# VS1053_Demo.net
KiCad netlist of a schematic drawn in EAGLE
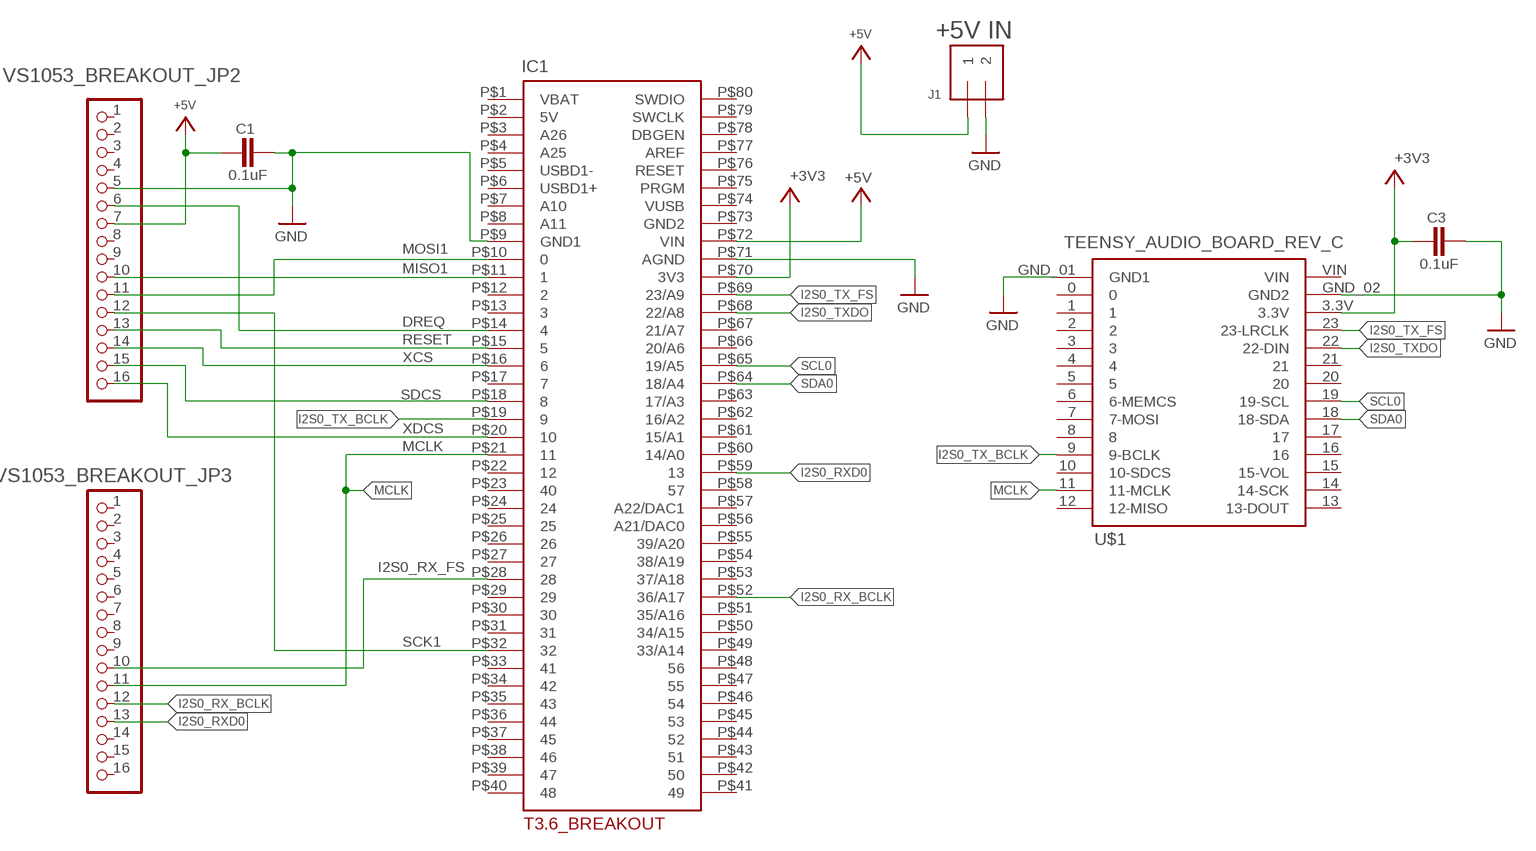
[diagram p0: schematic, sheet 1]

(export (version "E")
  (design (tool "Eeschema 10.0.6"))
  (components
    (comp (ref "C1")
      (value "0.1uF")
      (footprint "eagle-import:CAP-PTH-SMALL-KIT")
      (libsource (lib "eagle-import") (part "0.1UF-KIT-EZ-50V-20%"))
    )
    (comp (ref "C3")
      (value "0.1uF")
      (footprint "eagle-import:CAP-PTH-SMALL-KIT")
      (libsource (lib "eagle-import") (part "0.1UF-KIT-EZ-50V-20%"))
    )
    (comp (ref "IC1")
      (value "T3.6_BREAKOUT")
      (footprint "eagle-import:T3.6_BREAKOUT")
      (libsource (lib "eagle-import") (part "T3.6_BREAKOUT"))
    )
    (comp (ref "J1")
      (value "TERMBLOCK_1X2")
      (footprint "eagle-import:TERMBLOCK_1X2-3.5MM")
      (libsource (lib "eagle-import") (part "TERMBLOCK_1X2"))
    )
    (comp (ref "U$1")
      (value "TEENSY_AUDIO_BOARD_REV_C")
      (footprint "eagle-import:TEENSY_AUDIO_BOARD")
      (libsource (lib "eagle-import") (part "TEENSY_AUDIO_BOARD_REV_C"))
    )
    (comp (ref "VS1053_BREAKOUT_JP2")
      (value "HEADER-1X16ROUND")
      (footprint "eagle-import:1X16_ROUND")
      (libsource (lib "eagle-import") (part "HEADER-1X16ROUND"))
    )
    (comp (ref "VS1053_BREAKOUT_JP3")
      (value "HEADER-1X16ROUND")
      (footprint "eagle-import:1X16_ROUND")
      (libsource (lib "eagle-import") (part "HEADER-1X16ROUND"))
    )
  )
  (nets
    (net (code "1") (name "+3V3") (class "Default")
      (node (ref "C3") (pin "1") (pinfunction "1_1") (pintype "passive"))
      (node (ref "IC1") (pin "P$70") (pinfunction "3V3_P$70") (pintype "bidirectional"))
      (node (ref "U$1") (pin "3.3V") (pinfunction "3.3V_3.3V") (pintype "bidirectional"))
    )
    (net (code "2") (name "+5V") (class "Default")
      (node (ref "C1") (pin "1") (pinfunction "1_1") (pintype "passive"))
      (node (ref "IC1") (pin "P$72") (pinfunction "VIN_P$72") (pintype "bidirectional"))
      (node (ref "J1") (pin "1") (pinfunction "1_1") (pintype "passive"))
      (node (ref "VS1053_BREAKOUT_JP2") (pin "7") (pinfunction "7_7") (pintype "passive"))
    )
    (net (code "3") (name "/DREQ") (class "Default")
      (node (ref "IC1") (pin "P$14") (pinfunction "4_P$14") (pintype "bidirectional"))
      (node (ref "VS1053_BREAKOUT_JP2") (pin "6") (pinfunction "6_6") (pintype "passive"))
    )
    (net (code "4") (name "/I2S0_RX_FS") (class "Default")
      (node (ref "IC1") (pin "P$28") (pinfunction "28_P$28") (pintype "bidirectional"))
      (node (ref "VS1053_BREAKOUT_JP3") (pin "10") (pinfunction "10_10") (pintype "passive"))
    )
    (net (code "5") (name "/MISO1") (class "Default")
      (node (ref "IC1") (pin "P$11") (pinfunction "1_P$11") (pintype "bidirectional"))
      (node (ref "VS1053_BREAKOUT_JP2") (pin "10") (pinfunction "10_10") (pintype "passive"))
    )
    (net (code "6") (name "/MOSI1") (class "Default")
      (node (ref "IC1") (pin "P$10") (pinfunction "0_P$10") (pintype "bidirectional"))
      (node (ref "VS1053_BREAKOUT_JP2") (pin "11") (pinfunction "11_11") (pintype "passive"))
    )
    (net (code "7") (name "/RESET") (class "Default")
      (node (ref "IC1") (pin "P$15") (pinfunction "5_P$15") (pintype "bidirectional"))
      (node (ref "VS1053_BREAKOUT_JP2") (pin "13") (pinfunction "13_13") (pintype "passive"))
    )
    (net (code "8") (name "/SCK1") (class "Default")
      (node (ref "IC1") (pin "P$32") (pinfunction "32_P$32") (pintype "bidirectional"))
      (node (ref "VS1053_BREAKOUT_JP2") (pin "12") (pinfunction "12_12") (pintype "passive"))
    )
    (net (code "9") (name "/SDCS") (class "Default")
      (node (ref "IC1") (pin "P$18") (pinfunction "8_P$18") (pintype "bidirectional"))
      (node (ref "VS1053_BREAKOUT_JP2") (pin "15") (pinfunction "15_15") (pintype "passive"))
    )
    (net (code "10") (name "/XCS") (class "Default")
      (node (ref "IC1") (pin "P$16") (pinfunction "6_P$16") (pintype "bidirectional"))
      (node (ref "VS1053_BREAKOUT_JP2") (pin "14") (pinfunction "14_14") (pintype "passive"))
    )
    (net (code "11") (name "/XDCS") (class "Default")
      (node (ref "IC1") (pin "P$20") (pinfunction "10_P$20") (pintype "bidirectional"))
      (node (ref "VS1053_BREAKOUT_JP2") (pin "16") (pinfunction "16_16") (pintype "passive"))
    )
    (net (code "12") (name "GND") (class "Default")
      (node (ref "C1") (pin "2") (pinfunction "2_2") (pintype "passive"))
      (node (ref "C3") (pin "2") (pinfunction "2_2") (pintype "passive"))
      (node (ref "IC1") (pin "P$71") (pinfunction "AGND_P$71") (pintype "bidirectional"))
      (node (ref "IC1") (pin "P$9") (pinfunction "GND1_P$9") (pintype "bidirectional"))
      (node (ref "J1") (pin "2") (pinfunction "2_2") (pintype "passive"))
      (node (ref "U$1") (pin "GND_01") (pinfunction "GND1_GND_01") (pintype "bidirectional"))
      (node (ref "U$1") (pin "GND_02") (pinfunction "GND2_GND_02") (pintype "bidirectional"))
      (node (ref "VS1053_BREAKOUT_JP2") (pin "5") (pinfunction "5_5") (pintype "passive"))
    )
    (net (code "13") (name "I2S0_RXD0") (class "Default")
      (node (ref "IC1") (pin "P$59") (pinfunction "13_P$59") (pintype "bidirectional"))
      (node (ref "VS1053_BREAKOUT_JP3") (pin "13") (pinfunction "13_13") (pintype "passive"))
    )
    (net (code "14") (name "I2S0_RX_BCLK") (class "Default")
      (node (ref "IC1") (pin "P$52") (pinfunction "36/A17_P$52") (pintype "bidirectional"))
      (node (ref "VS1053_BREAKOUT_JP3") (pin "12") (pinfunction "12_12") (pintype "passive"))
    )
    (net (code "15") (name "I2S0_TXDO") (class "Default")
      (node (ref "IC1") (pin "P$68") (pinfunction "22/A8_P$68") (pintype "bidirectional"))
      (node (ref "U$1") (pin "22") (pinfunction "22-DIN_22") (pintype "bidirectional"))
    )
    (net (code "16") (name "I2S0_TX_BCLK") (class "Default")
      (node (ref "IC1") (pin "P$19") (pinfunction "9_P$19") (pintype "bidirectional"))
      (node (ref "U$1") (pin "9") (pinfunction "9-BCLK_9") (pintype "bidirectional"))
    )
    (net (code "17") (name "I2S0_TX_FS") (class "Default")
      (node (ref "IC1") (pin "P$69") (pinfunction "23/A9_P$69") (pintype "bidirectional"))
      (node (ref "U$1") (pin "23") (pinfunction "23-LRCLK_23") (pintype "bidirectional"))
    )
    (net (code "18") (name "MCLK") (class "Default")
      (node (ref "IC1") (pin "P$21") (pinfunction "11_P$21") (pintype "bidirectional"))
      (node (ref "U$1") (pin "11") (pinfunction "11-MCLK_11") (pintype "bidirectional"))
      (node (ref "VS1053_BREAKOUT_JP3") (pin "11") (pinfunction "11_11") (pintype "passive"))
    )
    (net (code "19") (name "SCL0") (class "Default")
      (node (ref "IC1") (pin "P$65") (pinfunction "19/A5_P$65") (pintype "bidirectional"))
      (node (ref "U$1") (pin "19") (pinfunction "19-SCL_19") (pintype "bidirectional"))
    )
    (net (code "20") (name "SDA0") (class "Default")
      (node (ref "IC1") (pin "P$64") (pinfunction "18/A4_P$64") (pintype "bidirectional"))
      (node (ref "U$1") (pin "18") (pinfunction "18-SDA_18") (pintype "bidirectional"))
    )
    (net (code "21") (name "unconnected-(IC1-2-PadP$12)") (class "Default")
      (node (ref "IC1") (pin "P$12") (pinfunction "2_P$12") (pintype "bidirectional"))
    )
    (net (code "22") (name "unconnected-(IC1-3-PadP$13)") (class "Default")
      (node (ref "IC1") (pin "P$13") (pinfunction "3_P$13") (pintype "bidirectional"))
    )
    (net (code "23") (name "unconnected-(IC1-5V-PadP$2)") (class "Default")
      (node (ref "IC1") (pin "P$2") (pinfunction "5V_P$2") (pintype "bidirectional"))
    )
    (net (code "24") (name "unconnected-(IC1-7-PadP$17)") (class "Default")
      (node (ref "IC1") (pin "P$17") (pinfunction "7_P$17") (pintype "bidirectional"))
    )
    (net (code "25") (name "unconnected-(IC1-12-PadP$22)") (class "Default")
      (node (ref "IC1") (pin "P$22") (pinfunction "12_P$22") (pintype "bidirectional"))
    )
    (net (code "26") (name "unconnected-(IC1-14{slash}A0-PadP$60)") (class "Default")
      (node (ref "IC1") (pin "P$60") (pinfunction "14/A0_P$60") (pintype "bidirectional"))
    )
    (net (code "27") (name "unconnected-(IC1-15{slash}A1-PadP$61)") (class "Default")
      (node (ref "IC1") (pin "P$61") (pinfunction "15/A1_P$61") (pintype "bidirectional"))
    )
    (net (code "28") (name "unconnected-(IC1-16{slash}A2-PadP$62)") (class "Default")
      (node (ref "IC1") (pin "P$62") (pinfunction "16/A2_P$62") (pintype "bidirectional"))
    )
    (net (code "29") (name "unconnected-(IC1-17{slash}A3-PadP$63)") (class "Default")
      (node (ref "IC1") (pin "P$63") (pinfunction "17/A3_P$63") (pintype "bidirectional"))
    )
    (net (code "30") (name "unconnected-(IC1-20{slash}A6-PadP$66)") (class "Default")
      (node (ref "IC1") (pin "P$66") (pinfunction "20/A6_P$66") (pintype "bidirectional"))
    )
    (net (code "31") (name "unconnected-(IC1-21{slash}A7-PadP$67)") (class "Default")
      (node (ref "IC1") (pin "P$67") (pinfunction "21/A7_P$67") (pintype "bidirectional"))
    )
    (net (code "32") (name "unconnected-(IC1-24-PadP$24)") (class "Default")
      (node (ref "IC1") (pin "P$24") (pinfunction "24_P$24") (pintype "bidirectional"))
    )
    (net (code "33") (name "unconnected-(IC1-25-PadP$25)") (class "Default")
      (node (ref "IC1") (pin "P$25") (pinfunction "25_P$25") (pintype "bidirectional"))
    )
    (net (code "34") (name "unconnected-(IC1-26-PadP$26)") (class "Default")
      (node (ref "IC1") (pin "P$26") (pinfunction "26_P$26") (pintype "bidirectional"))
    )
    (net (code "35") (name "unconnected-(IC1-27-PadP$27)") (class "Default")
      (node (ref "IC1") (pin "P$27") (pinfunction "27_P$27") (pintype "bidirectional"))
    )
    (net (code "36") (name "unconnected-(IC1-29-PadP$29)") (class "Default")
      (node (ref "IC1") (pin "P$29") (pinfunction "29_P$29") (pintype "bidirectional"))
    )
    (net (code "37") (name "unconnected-(IC1-30-PadP$30)") (class "Default")
      (node (ref "IC1") (pin "P$30") (pinfunction "30_P$30") (pintype "bidirectional"))
    )
    (net (code "38") (name "unconnected-(IC1-31-PadP$31)") (class "Default")
      (node (ref "IC1") (pin "P$31") (pinfunction "31_P$31") (pintype "bidirectional"))
    )
    (net (code "39") (name "unconnected-(IC1-33{slash}A14-PadP$49)") (class "Default")
      (node (ref "IC1") (pin "P$49") (pinfunction "33/A14_P$49") (pintype "bidirectional"))
    )
    (net (code "40") (name "unconnected-(IC1-34{slash}A15-PadP$50)") (class "Default")
      (node (ref "IC1") (pin "P$50") (pinfunction "34/A15_P$50") (pintype "bidirectional"))
    )
    (net (code "41") (name "unconnected-(IC1-35{slash}A16-PadP$51)") (class "Default")
      (node (ref "IC1") (pin "P$51") (pinfunction "35/A16_P$51") (pintype "bidirectional"))
    )
    (net (code "42") (name "unconnected-(IC1-37{slash}A18-PadP$53)") (class "Default")
      (node (ref "IC1") (pin "P$53") (pinfunction "37/A18_P$53") (pintype "bidirectional"))
    )
    (net (code "43") (name "unconnected-(IC1-38{slash}A19-PadP$54)") (class "Default")
      (node (ref "IC1") (pin "P$54") (pinfunction "38/A19_P$54") (pintype "bidirectional"))
    )
    (net (code "44") (name "unconnected-(IC1-39{slash}A20-PadP$55)") (class "Default")
      (node (ref "IC1") (pin "P$55") (pinfunction "39/A20_P$55") (pintype "bidirectional"))
    )
    (net (code "45") (name "unconnected-(IC1-40-PadP$23)") (class "Default")
      (node (ref "IC1") (pin "P$23") (pinfunction "40_P$23") (pintype "bidirectional"))
    )
    (net (code "46") (name "unconnected-(IC1-41-PadP$33)") (class "Default")
      (node (ref "IC1") (pin "P$33") (pinfunction "41_P$33") (pintype "bidirectional"))
    )
    (net (code "47") (name "unconnected-(IC1-42-PadP$34)") (class "Default")
      (node (ref "IC1") (pin "P$34") (pinfunction "42_P$34") (pintype "bidirectional"))
    )
    (net (code "48") (name "unconnected-(IC1-43-PadP$35)") (class "Default")
      (node (ref "IC1") (pin "P$35") (pinfunction "43_P$35") (pintype "bidirectional"))
    )
    (net (code "49") (name "unconnected-(IC1-44-PadP$36)") (class "Default")
      (node (ref "IC1") (pin "P$36") (pinfunction "44_P$36") (pintype "bidirectional"))
    )
    (net (code "50") (name "unconnected-(IC1-45-PadP$37)") (class "Default")
      (node (ref "IC1") (pin "P$37") (pinfunction "45_P$37") (pintype "bidirectional"))
    )
    (net (code "51") (name "unconnected-(IC1-46-PadP$38)") (class "Default")
      (node (ref "IC1") (pin "P$38") (pinfunction "46_P$38") (pintype "bidirectional"))
    )
    (net (code "52") (name "unconnected-(IC1-47-PadP$39)") (class "Default")
      (node (ref "IC1") (pin "P$39") (pinfunction "47_P$39") (pintype "bidirectional"))
    )
    (net (code "53") (name "unconnected-(IC1-48-PadP$40)") (class "Default")
      (node (ref "IC1") (pin "P$40") (pinfunction "48_P$40") (pintype "bidirectional"))
    )
    (net (code "54") (name "unconnected-(IC1-49-PadP$41)") (class "Default")
      (node (ref "IC1") (pin "P$41") (pinfunction "49_P$41") (pintype "bidirectional"))
    )
    (net (code "55") (name "unconnected-(IC1-50-PadP$42)") (class "Default")
      (node (ref "IC1") (pin "P$42") (pinfunction "50_P$42") (pintype "bidirectional"))
    )
    (net (code "56") (name "unconnected-(IC1-51-PadP$43)") (class "Default")
      (node (ref "IC1") (pin "P$43") (pinfunction "51_P$43") (pintype "bidirectional"))
    )
    (net (code "57") (name "unconnected-(IC1-52-PadP$44)") (class "Default")
      (node (ref "IC1") (pin "P$44") (pinfunction "52_P$44") (pintype "bidirectional"))
    )
    (net (code "58") (name "unconnected-(IC1-53-PadP$45)") (class "Default")
      (node (ref "IC1") (pin "P$45") (pinfunction "53_P$45") (pintype "bidirectional"))
    )
    (net (code "59") (name "unconnected-(IC1-54-PadP$46)") (class "Default")
      (node (ref "IC1") (pin "P$46") (pinfunction "54_P$46") (pintype "bidirectional"))
    )
    (net (code "60") (name "unconnected-(IC1-55-PadP$47)") (class "Default")
      (node (ref "IC1") (pin "P$47") (pinfunction "55_P$47") (pintype "bidirectional"))
    )
    (net (code "61") (name "unconnected-(IC1-56-PadP$48)") (class "Default")
      (node (ref "IC1") (pin "P$48") (pinfunction "56_P$48") (pintype "bidirectional"))
    )
    (net (code "62") (name "unconnected-(IC1-57-PadP$58)") (class "Default")
      (node (ref "IC1") (pin "P$58") (pinfunction "57_P$58") (pintype "bidirectional"))
    )
    (net (code "63") (name "unconnected-(IC1-A10-PadP$7)") (class "Default")
      (node (ref "IC1") (pin "P$7") (pinfunction "A10_P$7") (pintype "bidirectional"))
    )
    (net (code "64") (name "unconnected-(IC1-A11-PadP$8)") (class "Default")
      (node (ref "IC1") (pin "P$8") (pinfunction "A11_P$8") (pintype "bidirectional"))
    )
    (net (code "65") (name "unconnected-(IC1-A21{slash}DAC0-PadP$56)") (class "Default")
      (node (ref "IC1") (pin "P$56") (pinfunction "A21/DAC0_P$56") (pintype "bidirectional"))
    )
    (net (code "66") (name "unconnected-(IC1-A22{slash}DAC1-PadP$57)") (class "Default")
      (node (ref "IC1") (pin "P$57") (pinfunction "A22/DAC1_P$57") (pintype "bidirectional"))
    )
    (net (code "67") (name "unconnected-(IC1-A25-PadP$4)") (class "Default")
      (node (ref "IC1") (pin "P$4") (pinfunction "A25_P$4") (pintype "bidirectional"))
    )
    (net (code "68") (name "unconnected-(IC1-A26-PadP$3)") (class "Default")
      (node (ref "IC1") (pin "P$3") (pinfunction "A26_P$3") (pintype "bidirectional"))
    )
    (net (code "69") (name "unconnected-(IC1-AREF-PadP$77)") (class "Default")
      (node (ref "IC1") (pin "P$77") (pinfunction "AREF_P$77") (pintype "bidirectional"))
    )
    (net (code "70") (name "unconnected-(IC1-DBGEN-PadP$78)") (class "Default")
      (node (ref "IC1") (pin "P$78") (pinfunction "DBGEN_P$78") (pintype "bidirectional"))
    )
    (net (code "71") (name "unconnected-(IC1-GND2-PadP$73)") (class "Default")
      (node (ref "IC1") (pin "P$73") (pinfunction "GND2_P$73") (pintype "bidirectional"))
    )
    (net (code "72") (name "unconnected-(IC1-PRGM-PadP$75)") (class "Default")
      (node (ref "IC1") (pin "P$75") (pinfunction "PRGM_P$75") (pintype "bidirectional"))
    )
    (net (code "73") (name "unconnected-(IC1-RESET-PadP$76)") (class "Default")
      (node (ref "IC1") (pin "P$76") (pinfunction "RESET_P$76") (pintype "bidirectional"))
    )
    (net (code "74") (name "unconnected-(IC1-SWCLK-PadP$79)") (class "Default")
      (node (ref "IC1") (pin "P$79") (pinfunction "SWCLK_P$79") (pintype "bidirectional"))
    )
    (net (code "75") (name "unconnected-(IC1-SWDIO-PadP$80)") (class "Default")
      (node (ref "IC1") (pin "P$80") (pinfunction "SWDIO_P$80") (pintype "bidirectional"))
    )
    (net (code "76") (name "unconnected-(IC1-USBD1+-PadP$6)") (class "Default")
      (node (ref "IC1") (pin "P$6") (pinfunction "USBD1+_P$6") (pintype "bidirectional"))
    )
    (net (code "77") (name "unconnected-(IC1-USBD1--PadP$5)") (class "Default")
      (node (ref "IC1") (pin "P$5") (pinfunction "USBD1-_P$5") (pintype "bidirectional"))
    )
    (net (code "78") (name "unconnected-(IC1-VBAT-PadP$1)") (class "Default")
      (node (ref "IC1") (pin "P$1") (pinfunction "VBAT_P$1") (pintype "bidirectional"))
    )
    (net (code "79") (name "unconnected-(IC1-VUSB-PadP$74)") (class "Default")
      (node (ref "IC1") (pin "P$74") (pinfunction "VUSB_P$74") (pintype "bidirectional"))
    )
    (net (code "80") (name "unconnected-(U$1-6-MEMCS-Pad6)") (class "Default")
      (node (ref "U$1") (pin "6") (pinfunction "6-MEMCS_6") (pintype "bidirectional"))
    )
    (net (code "81") (name "unconnected-(U$1-7-MOSI-Pad7)") (class "Default")
      (node (ref "U$1") (pin "7") (pinfunction "7-MOSI_7") (pintype "bidirectional"))
    )
    (net (code "82") (name "unconnected-(U$1-10-SDCS-Pad10)") (class "Default")
      (node (ref "U$1") (pin "10") (pinfunction "10-SDCS_10") (pintype "bidirectional"))
    )
    (net (code "83") (name "unconnected-(U$1-12-MISO-Pad12)") (class "Default")
      (node (ref "U$1") (pin "12") (pinfunction "12-MISO_12") (pintype "bidirectional"))
    )
    (net (code "84") (name "unconnected-(U$1-13-DOUT-Pad13)") (class "Default")
      (node (ref "U$1") (pin "13") (pinfunction "13-DOUT_13") (pintype "bidirectional"))
    )
    (net (code "85") (name "unconnected-(U$1-14-SCK-Pad14)") (class "Default")
      (node (ref "U$1") (pin "14") (pinfunction "14-SCK_14") (pintype "bidirectional"))
    )
    (net (code "86") (name "unconnected-(U$1-15-VOL-Pad15)") (class "Default")
      (node (ref "U$1") (pin "15") (pinfunction "15-VOL_15") (pintype "bidirectional"))
    )
    (net (code "87") (name "unconnected-(U$1-Pad0)") (class "Default")
      (node (ref "U$1") (pin "0") (pinfunction "0_0") (pintype "bidirectional"))
    )
    (net (code "88") (name "unconnected-(U$1-Pad1)") (class "Default")
      (node (ref "U$1") (pin "1") (pinfunction "1_1") (pintype "bidirectional"))
    )
    (net (code "89") (name "unconnected-(U$1-Pad2)") (class "Default")
      (node (ref "U$1") (pin "2") (pinfunction "2_2") (pintype "bidirectional"))
    )
    (net (code "90") (name "unconnected-(U$1-Pad3)") (class "Default")
      (node (ref "U$1") (pin "3") (pinfunction "3_3") (pintype "bidirectional"))
    )
    (net (code "91") (name "unconnected-(U$1-Pad4)") (class "Default")
      (node (ref "U$1") (pin "4") (pinfunction "4_4") (pintype "bidirectional"))
    )
    (net (code "92") (name "unconnected-(U$1-Pad5)") (class "Default")
      (node (ref "U$1") (pin "5") (pinfunction "5_5") (pintype "bidirectional"))
    )
    (net (code "93") (name "unconnected-(U$1-Pad8)") (class "Default")
      (node (ref "U$1") (pin "8") (pinfunction "8_8") (pintype "bidirectional"))
    )
    (net (code "94") (name "unconnected-(U$1-Pad16)") (class "Default")
      (node (ref "U$1") (pin "16") (pinfunction "16_16") (pintype "bidirectional"))
    )
    (net (code "95") (name "unconnected-(U$1-Pad17)") (class "Default")
      (node (ref "U$1") (pin "17") (pinfunction "17_17") (pintype "bidirectional"))
    )
    (net (code "96") (name "unconnected-(U$1-Pad20)") (class "Default")
      (node (ref "U$1") (pin "20") (pinfunction "20_20") (pintype "bidirectional"))
    )
    (net (code "97") (name "unconnected-(U$1-Pad21)") (class "Default")
      (node (ref "U$1") (pin "21") (pinfunction "21_21") (pintype "bidirectional"))
    )
    (net (code "98") (name "unconnected-(U$1-PadVIN)") (class "Default")
      (node (ref "U$1") (pin "VIN") (pinfunction "VIN_VIN") (pintype "bidirectional"))
    )
    (net (code "99") (name "unconnected-(VS1053_BREAKOUT_JP2-Pad1)") (class "Default")
      (node (ref "VS1053_BREAKOUT_JP2") (pin "1") (pinfunction "1_1") (pintype "passive"))
    )
    (net (code "100") (name "unconnected-(VS1053_BREAKOUT_JP2-Pad2)") (class "Default")
      (node (ref "VS1053_BREAKOUT_JP2") (pin "2") (pinfunction "2_2") (pintype "passive"))
    )
    (net (code "101") (name "unconnected-(VS1053_BREAKOUT_JP2-Pad3)") (class "Default")
      (node (ref "VS1053_BREAKOUT_JP2") (pin "3") (pinfunction "3_3") (pintype "passive"))
    )
    (net (code "102") (name "unconnected-(VS1053_BREAKOUT_JP2-Pad4)") (class "Default")
      (node (ref "VS1053_BREAKOUT_JP2") (pin "4") (pinfunction "4_4") (pintype "passive"))
    )
    (net (code "103") (name "unconnected-(VS1053_BREAKOUT_JP2-Pad8)") (class "Default")
      (node (ref "VS1053_BREAKOUT_JP2") (pin "8") (pinfunction "8_8") (pintype "passive"))
    )
    (net (code "104") (name "unconnected-(VS1053_BREAKOUT_JP2-Pad9)") (class "Default")
      (node (ref "VS1053_BREAKOUT_JP2") (pin "9") (pinfunction "9_9") (pintype "passive"))
    )
    (net (code "105") (name "unconnected-(VS1053_BREAKOUT_JP3-Pad1)") (class "Default")
      (node (ref "VS1053_BREAKOUT_JP3") (pin "1") (pinfunction "1_1") (pintype "passive"))
    )
    (net (code "106") (name "unconnected-(VS1053_BREAKOUT_JP3-Pad2)") (class "Default")
      (node (ref "VS1053_BREAKOUT_JP3") (pin "2") (pinfunction "2_2") (pintype "passive"))
    )
    (net (code "107") (name "unconnected-(VS1053_BREAKOUT_JP3-Pad3)") (class "Default")
      (node (ref "VS1053_BREAKOUT_JP3") (pin "3") (pinfunction "3_3") (pintype "passive"))
    )
    (net (code "108") (name "unconnected-(VS1053_BREAKOUT_JP3-Pad4)") (class "Default")
      (node (ref "VS1053_BREAKOUT_JP3") (pin "4") (pinfunction "4_4") (pintype "passive"))
    )
    (net (code "109") (name "unconnected-(VS1053_BREAKOUT_JP3-Pad5)") (class "Default")
      (node (ref "VS1053_BREAKOUT_JP3") (pin "5") (pinfunction "5_5") (pintype "passive"))
    )
    (net (code "110") (name "unconnected-(VS1053_BREAKOUT_JP3-Pad6)") (class "Default")
      (node (ref "VS1053_BREAKOUT_JP3") (pin "6") (pinfunction "6_6") (pintype "passive"))
    )
    (net (code "111") (name "unconnected-(VS1053_BREAKOUT_JP3-Pad7)") (class "Default")
      (node (ref "VS1053_BREAKOUT_JP3") (pin "7") (pinfunction "7_7") (pintype "passive"))
    )
    (net (code "112") (name "unconnected-(VS1053_BREAKOUT_JP3-Pad8)") (class "Default")
      (node (ref "VS1053_BREAKOUT_JP3") (pin "8") (pinfunction "8_8") (pintype "passive"))
    )
    (net (code "113") (name "unconnected-(VS1053_BREAKOUT_JP3-Pad9)") (class "Default")
      (node (ref "VS1053_BREAKOUT_JP3") (pin "9") (pinfunction "9_9") (pintype "passive"))
    )
    (net (code "114") (name "unconnected-(VS1053_BREAKOUT_JP3-Pad14)") (class "Default")
      (node (ref "VS1053_BREAKOUT_JP3") (pin "14") (pinfunction "14_14") (pintype "passive"))
    )
    (net (code "115") (name "unconnected-(VS1053_BREAKOUT_JP3-Pad15)") (class "Default")
      (node (ref "VS1053_BREAKOUT_JP3") (pin "15") (pinfunction "15_15") (pintype "passive"))
    )
    (net (code "116") (name "unconnected-(VS1053_BREAKOUT_JP3-Pad16)") (class "Default")
      (node (ref "VS1053_BREAKOUT_JP3") (pin "16") (pinfunction "16_16") (pintype "passive"))
    )
  )
)
